# Connectors.net
KiCad netlist of a schematic drawn in Altium Designer
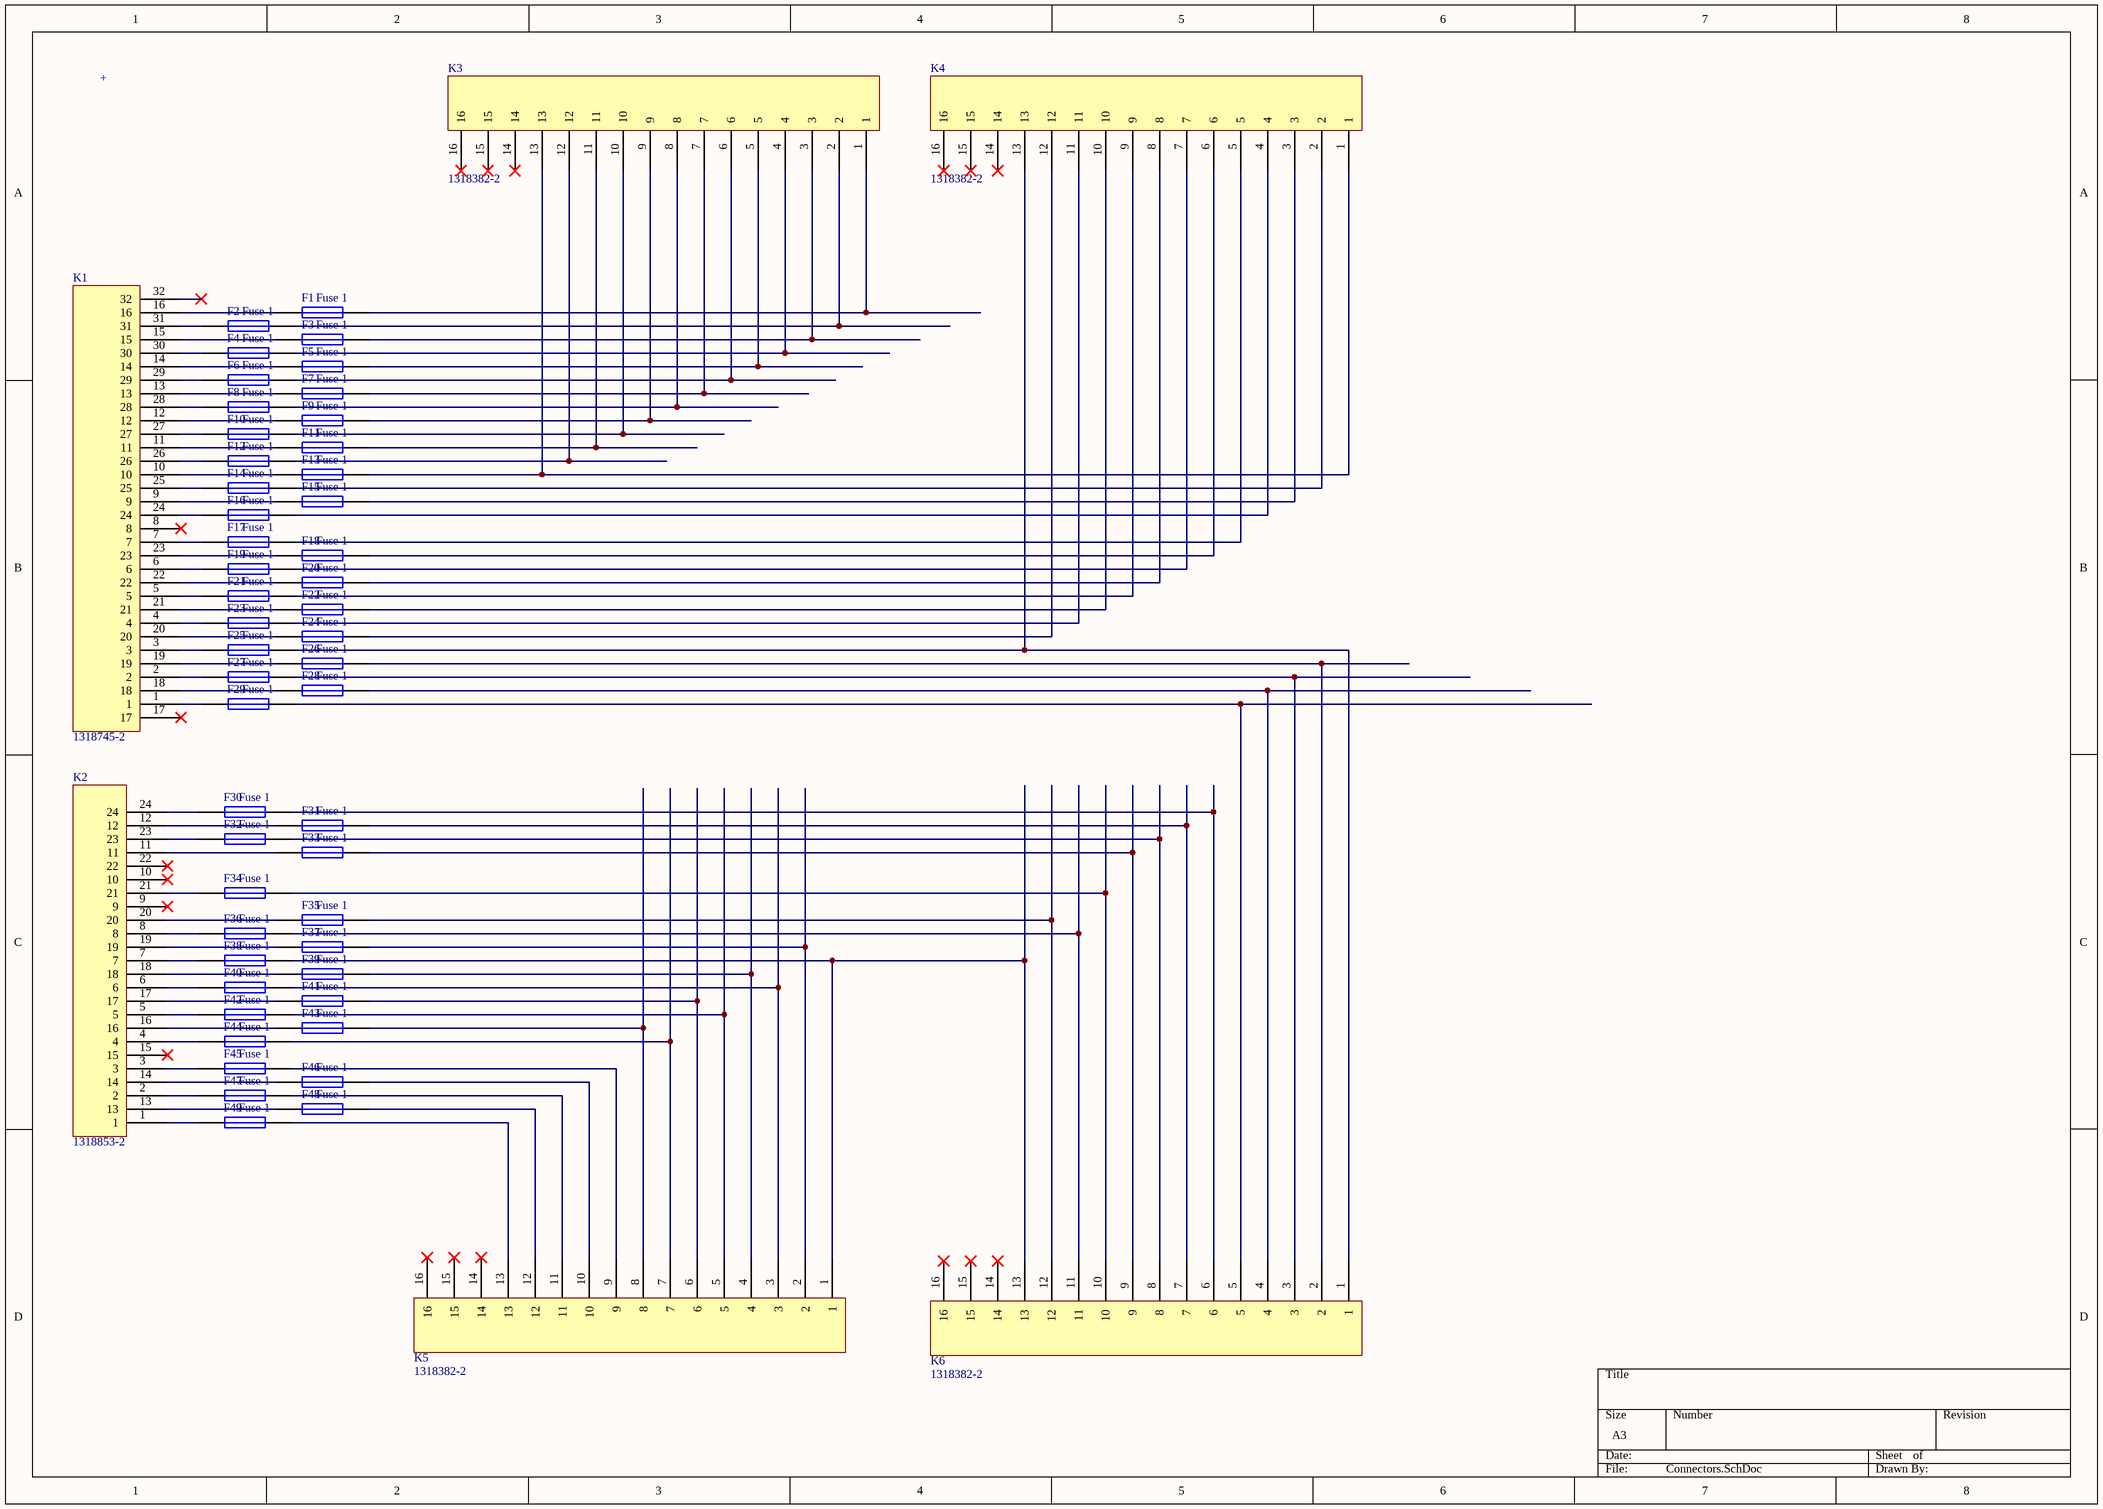
[diagram p0: Connectors.SchDoc]

(export (version "E")
  (design (tool "Eeschema 10.0.6"))
  (components
    (comp (ref "F1")
      (value "Fuse 1")
      (footprint "C1206")
      (description "Fuse")
      (fields (field (name "PUBLISHER") "Altium Limited"))
      (libsource (lib "Miscellaneous Devices") (part "Fuse 1"))
    )
    (comp (ref "F2")
      (value "Fuse 1")
      (footprint "C1206")
      (description "Fuse")
      (fields (field (name "PUBLISHER") "Altium Limited"))
      (libsource (lib "Miscellaneous Devices") (part "Fuse 1"))
    )
    (comp (ref "F3")
      (value "Fuse 1")
      (footprint "C1206")
      (description "Fuse")
      (fields (field (name "PUBLISHER") "Altium Limited"))
      (libsource (lib "Miscellaneous Devices") (part "Fuse 1"))
    )
    (comp (ref "F4")
      (value "Fuse 1")
      (footprint "C1206")
      (description "Fuse")
      (fields (field (name "PUBLISHER") "Altium Limited"))
      (libsource (lib "Miscellaneous Devices") (part "Fuse 1"))
    )
    (comp (ref "F5")
      (value "Fuse 1")
      (footprint "C1206")
      (description "Fuse")
      (fields (field (name "PUBLISHER") "Altium Limited"))
      (libsource (lib "Miscellaneous Devices") (part "Fuse 1"))
    )
    (comp (ref "F6")
      (value "Fuse 1")
      (footprint "C1206")
      (description "Fuse")
      (fields (field (name "PUBLISHER") "Altium Limited"))
      (libsource (lib "Miscellaneous Devices") (part "Fuse 1"))
    )
    (comp (ref "F7")
      (value "Fuse 1")
      (footprint "C1206")
      (description "Fuse")
      (fields (field (name "PUBLISHER") "Altium Limited"))
      (libsource (lib "Miscellaneous Devices") (part "Fuse 1"))
    )
    (comp (ref "F8")
      (value "Fuse 1")
      (footprint "C1206")
      (description "Fuse")
      (fields (field (name "PUBLISHER") "Altium Limited"))
      (libsource (lib "Miscellaneous Devices") (part "Fuse 1"))
    )
    (comp (ref "F9")
      (value "Fuse 1")
      (footprint "C1206")
      (description "Fuse")
      (fields (field (name "PUBLISHER") "Altium Limited"))
      (libsource (lib "Miscellaneous Devices") (part "Fuse 1"))
    )
    (comp (ref "F10")
      (value "Fuse 1")
      (footprint "C1206")
      (description "Fuse")
      (fields (field (name "PUBLISHER") "Altium Limited"))
      (libsource (lib "Miscellaneous Devices") (part "Fuse 1"))
    )
    (comp (ref "F11")
      (value "Fuse 1")
      (footprint "C1206")
      (description "Fuse")
      (fields (field (name "PUBLISHER") "Altium Limited"))
      (libsource (lib "Miscellaneous Devices") (part "Fuse 1"))
    )
    (comp (ref "F12")
      (value "Fuse 1")
      (footprint "C1206")
      (description "Fuse")
      (fields (field (name "PUBLISHER") "Altium Limited"))
      (libsource (lib "Miscellaneous Devices") (part "Fuse 1"))
    )
    (comp (ref "F13")
      (value "Fuse 1")
      (footprint "C1206")
      (description "Fuse")
      (fields (field (name "PUBLISHER") "Altium Limited"))
      (libsource (lib "Miscellaneous Devices") (part "Fuse 1"))
    )
    (comp (ref "F14")
      (value "Fuse 1")
      (footprint "C1206")
      (description "Fuse")
      (fields (field (name "PUBLISHER") "Altium Limited"))
      (libsource (lib "Miscellaneous Devices") (part "Fuse 1"))
    )
    (comp (ref "F15")
      (value "Fuse 1")
      (footprint "C1206")
      (description "Fuse")
      (fields (field (name "PUBLISHER") "Altium Limited"))
      (libsource (lib "Miscellaneous Devices") (part "Fuse 1"))
    )
    (comp (ref "F16")
      (value "Fuse 1")
      (footprint "C1206")
      (description "Fuse")
      (fields (field (name "PUBLISHER") "Altium Limited"))
      (libsource (lib "Miscellaneous Devices") (part "Fuse 1"))
    )
    (comp (ref "F17")
      (value "Fuse 1")
      (footprint "C1206")
      (description "Fuse")
      (fields (field (name "PUBLISHER") "Altium Limited"))
      (libsource (lib "Miscellaneous Devices") (part "Fuse 1"))
    )
    (comp (ref "F18")
      (value "Fuse 1")
      (footprint "C1206")
      (description "Fuse")
      (fields (field (name "PUBLISHER") "Altium Limited"))
      (libsource (lib "Miscellaneous Devices") (part "Fuse 1"))
    )
    (comp (ref "F19")
      (value "Fuse 1")
      (footprint "C1206")
      (description "Fuse")
      (fields (field (name "PUBLISHER") "Altium Limited"))
      (libsource (lib "Miscellaneous Devices") (part "Fuse 1"))
    )
    (comp (ref "F20")
      (value "Fuse 1")
      (footprint "C1206")
      (description "Fuse")
      (fields (field (name "PUBLISHER") "Altium Limited"))
      (libsource (lib "Miscellaneous Devices") (part "Fuse 1"))
    )
    (comp (ref "F21")
      (value "Fuse 1")
      (footprint "C1206")
      (description "Fuse")
      (fields (field (name "PUBLISHER") "Altium Limited"))
      (libsource (lib "Miscellaneous Devices") (part "Fuse 1"))
    )
    (comp (ref "F22")
      (value "Fuse 1")
      (footprint "C1206")
      (description "Fuse")
      (fields (field (name "PUBLISHER") "Altium Limited"))
      (libsource (lib "Miscellaneous Devices") (part "Fuse 1"))
    )
    (comp (ref "F23")
      (value "Fuse 1")
      (footprint "C1206")
      (description "Fuse")
      (fields (field (name "PUBLISHER") "Altium Limited"))
      (libsource (lib "Miscellaneous Devices") (part "Fuse 1"))
    )
    (comp (ref "F24")
      (value "Fuse 1")
      (footprint "C1206")
      (description "Fuse")
      (fields (field (name "PUBLISHER") "Altium Limited"))
      (libsource (lib "Miscellaneous Devices") (part "Fuse 1"))
    )
    (comp (ref "F25")
      (value "Fuse 1")
      (footprint "C1206")
      (description "Fuse")
      (fields (field (name "PUBLISHER") "Altium Limited"))
      (libsource (lib "Miscellaneous Devices") (part "Fuse 1"))
    )
    (comp (ref "F26")
      (value "Fuse 1")
      (footprint "C1206")
      (description "Fuse")
      (fields (field (name "PUBLISHER") "Altium Limited"))
      (libsource (lib "Miscellaneous Devices") (part "Fuse 1"))
    )
    (comp (ref "F27")
      (value "Fuse 1")
      (footprint "C1206")
      (description "Fuse")
      (fields (field (name "PUBLISHER") "Altium Limited"))
      (libsource (lib "Miscellaneous Devices") (part "Fuse 1"))
    )
    (comp (ref "F28")
      (value "Fuse 1")
      (footprint "C1206")
      (description "Fuse")
      (fields (field (name "PUBLISHER") "Altium Limited"))
      (libsource (lib "Miscellaneous Devices") (part "Fuse 1"))
    )
    (comp (ref "F29")
      (value "Fuse 1")
      (footprint "C1206")
      (description "Fuse")
      (fields (field (name "PUBLISHER") "Altium Limited"))
      (libsource (lib "Miscellaneous Devices") (part "Fuse 1"))
    )
    (comp (ref "F30")
      (value "Fuse 1")
      (footprint "C1206")
      (description "Fuse")
      (fields (field (name "PUBLISHER") "Altium Limited"))
      (libsource (lib "Miscellaneous Devices") (part "Fuse 1"))
    )
    (comp (ref "F31")
      (value "Fuse 1")
      (footprint "C1206")
      (description "Fuse")
      (fields (field (name "PUBLISHER") "Altium Limited"))
      (libsource (lib "Miscellaneous Devices") (part "Fuse 1"))
    )
    (comp (ref "F32")
      (value "Fuse 1")
      (footprint "C1206")
      (description "Fuse")
      (fields (field (name "PUBLISHER") "Altium Limited"))
      (libsource (lib "Miscellaneous Devices") (part "Fuse 1"))
    )
    (comp (ref "F33")
      (value "Fuse 1")
      (footprint "C1206")
      (description "Fuse")
      (fields (field (name "PUBLISHER") "Altium Limited"))
      (libsource (lib "Miscellaneous Devices") (part "Fuse 1"))
    )
    (comp (ref "F34")
      (value "Fuse 1")
      (footprint "C1206")
      (description "Fuse")
      (fields (field (name "PUBLISHER") "Altium Limited"))
      (libsource (lib "Miscellaneous Devices") (part "Fuse 1"))
    )
    (comp (ref "F35")
      (value "Fuse 1")
      (footprint "C1206")
      (description "Fuse")
      (fields (field (name "PUBLISHER") "Altium Limited"))
      (libsource (lib "Miscellaneous Devices") (part "Fuse 1"))
    )
    (comp (ref "F36")
      (value "Fuse 1")
      (footprint "C1206")
      (description "Fuse")
      (fields (field (name "PUBLISHER") "Altium Limited"))
      (libsource (lib "Miscellaneous Devices") (part "Fuse 1"))
    )
    (comp (ref "F37")
      (value "Fuse 1")
      (footprint "C1206")
      (description "Fuse")
      (fields (field (name "PUBLISHER") "Altium Limited"))
      (libsource (lib "Miscellaneous Devices") (part "Fuse 1"))
    )
    (comp (ref "F38")
      (value "Fuse 1")
      (footprint "C1206")
      (description "Fuse")
      (fields (field (name "PUBLISHER") "Altium Limited"))
      (libsource (lib "Miscellaneous Devices") (part "Fuse 1"))
    )
    (comp (ref "F39")
      (value "Fuse 1")
      (footprint "C1206")
      (description "Fuse")
      (fields (field (name "PUBLISHER") "Altium Limited"))
      (libsource (lib "Miscellaneous Devices") (part "Fuse 1"))
    )
    (comp (ref "F40")
      (value "Fuse 1")
      (footprint "C1206")
      (description "Fuse")
      (fields (field (name "PUBLISHER") "Altium Limited"))
      (libsource (lib "Miscellaneous Devices") (part "Fuse 1"))
    )
    (comp (ref "F41")
      (value "Fuse 1")
      (footprint "C1206")
      (description "Fuse")
      (fields (field (name "PUBLISHER") "Altium Limited"))
      (libsource (lib "Miscellaneous Devices") (part "Fuse 1"))
    )
    (comp (ref "F42")
      (value "Fuse 1")
      (footprint "C1206")
      (description "Fuse")
      (fields (field (name "PUBLISHER") "Altium Limited"))
      (libsource (lib "Miscellaneous Devices") (part "Fuse 1"))
    )
    (comp (ref "F43")
      (value "Fuse 1")
      (footprint "C1206")
      (description "Fuse")
      (fields (field (name "PUBLISHER") "Altium Limited"))
      (libsource (lib "Miscellaneous Devices") (part "Fuse 1"))
    )
    (comp (ref "F44")
      (value "Fuse 1")
      (footprint "C1206")
      (description "Fuse")
      (fields (field (name "PUBLISHER") "Altium Limited"))
      (libsource (lib "Miscellaneous Devices") (part "Fuse 1"))
    )
    (comp (ref "F45")
      (value "Fuse 1")
      (footprint "C1206")
      (description "Fuse")
      (fields (field (name "PUBLISHER") "Altium Limited"))
      (libsource (lib "Miscellaneous Devices") (part "Fuse 1"))
    )
    (comp (ref "F46")
      (value "Fuse 1")
      (footprint "C1206")
      (description "Fuse")
      (fields (field (name "PUBLISHER") "Altium Limited"))
      (libsource (lib "Miscellaneous Devices") (part "Fuse 1"))
    )
    (comp (ref "F47")
      (value "Fuse 1")
      (footprint "C1206")
      (description "Fuse")
      (fields (field (name "PUBLISHER") "Altium Limited"))
      (libsource (lib "Miscellaneous Devices") (part "Fuse 1"))
    )
    (comp (ref "F48")
      (value "Fuse 1")
      (footprint "C1206")
      (description "Fuse")
      (fields (field (name "PUBLISHER") "Altium Limited"))
      (libsource (lib "Miscellaneous Devices") (part "Fuse 1"))
    )
    (comp (ref "F49")
      (value "Fuse 1")
      (footprint "C1206")
      (description "Fuse")
      (fields (field (name "PUBLISHER") "Altium Limited"))
      (libsource (lib "Miscellaneous Devices") (part "Fuse 1"))
    )
    (comp (ref "K1")
      (value "1318745-2")
      (footprint "1318745-2")
      (libsource (lib "TE connectivity") (part "1318745-2"))
    )
    (comp (ref "K2")
      (value "1318853-2")
      (footprint "1318853-2")
      (libsource (lib "TE connectivity") (part "1318853-2"))
    )
    (comp (ref "K3") (value "1318382-2") (footprint "1318382-2") (libsource (lib "") (part "1318382-2_1")))
    (comp (ref "K4") (value "1318382-2") (footprint "1318382-2") (libsource (lib "") (part "1318382-2_1")))
    (comp (ref "K5")
      (value "1318382-2")
      (footprint "1318382-2")
      (libsource (lib "TE connectivity") (part "1318382-2"))
    )
    (comp (ref "K6")
      (value "1318382-2")
      (footprint "1318382-2")
      (libsource (lib "TE connectivity") (part "1318382-2"))
    )
  )
  (nets
    (net (code "1") (name "Net-(F1-Pad1)") (class "Default")
      (node (ref "F1") (pin "1") (pinfunction "1_1") (pintype "passive"))
      (node (ref "K1") (pin "16") (pinfunction "16_16") (pintype "passive"))
    )
    (net (code "2") (name "Net-(F1-Pad2)") (class "Default")
      (node (ref "F1") (pin "2") (pinfunction "2_2") (pintype "passive"))
      (node (ref "K3") (pin "1") (pinfunction "1_1") (pintype "passive"))
    )
    (net (code "3") (name "Net-(F2-Pad1)") (class "Default")
      (node (ref "F2") (pin "1") (pinfunction "1_1") (pintype "passive"))
      (node (ref "K1") (pin "31") (pinfunction "31_31") (pintype "passive"))
    )
    (net (code "4") (name "Net-(F2-Pad2)") (class "Default")
      (node (ref "F2") (pin "2") (pinfunction "2_2") (pintype "passive"))
      (node (ref "K3") (pin "2") (pinfunction "2_2") (pintype "passive"))
    )
    (net (code "5") (name "Net-(F3-Pad1)") (class "Default")
      (node (ref "F3") (pin "1") (pinfunction "1_1") (pintype "passive"))
      (node (ref "K1") (pin "15") (pinfunction "15_15") (pintype "passive"))
    )
    (net (code "6") (name "Net-(F3-Pad2)") (class "Default")
      (node (ref "F3") (pin "2") (pinfunction "2_2") (pintype "passive"))
      (node (ref "K3") (pin "3") (pinfunction "3_3") (pintype "passive"))
    )
    (net (code "7") (name "Net-(F4-Pad1)") (class "Default")
      (node (ref "F4") (pin "1") (pinfunction "1_1") (pintype "passive"))
      (node (ref "K1") (pin "30") (pinfunction "30_30") (pintype "passive"))
    )
    (net (code "8") (name "Net-(F4-Pad2)") (class "Default")
      (node (ref "F4") (pin "2") (pinfunction "2_2") (pintype "passive"))
      (node (ref "K3") (pin "4") (pinfunction "4_4") (pintype "passive"))
    )
    (net (code "9") (name "Net-(F5-Pad1)") (class "Default")
      (node (ref "F5") (pin "1") (pinfunction "1_1") (pintype "passive"))
      (node (ref "K1") (pin "14") (pinfunction "14_14") (pintype "passive"))
    )
    (net (code "10") (name "Net-(F5-Pad2)") (class "Default")
      (node (ref "F5") (pin "2") (pinfunction "2_2") (pintype "passive"))
      (node (ref "K3") (pin "5") (pinfunction "5_5") (pintype "passive"))
    )
    (net (code "11") (name "Net-(F6-Pad1)") (class "Default")
      (node (ref "F6") (pin "1") (pinfunction "1_1") (pintype "passive"))
      (node (ref "K1") (pin "29") (pinfunction "29_29") (pintype "passive"))
    )
    (net (code "12") (name "Net-(F6-Pad2)") (class "Default")
      (node (ref "F6") (pin "2") (pinfunction "2_2") (pintype "passive"))
      (node (ref "K3") (pin "6") (pinfunction "6_6") (pintype "passive"))
    )
    (net (code "13") (name "Net-(F7-Pad1)") (class "Default")
      (node (ref "F7") (pin "1") (pinfunction "1_1") (pintype "passive"))
      (node (ref "K1") (pin "13") (pinfunction "13_13") (pintype "passive"))
    )
    (net (code "14") (name "Net-(F7-Pad2)") (class "Default")
      (node (ref "F7") (pin "2") (pinfunction "2_2") (pintype "passive"))
      (node (ref "K3") (pin "7") (pinfunction "7_7") (pintype "passive"))
    )
    (net (code "15") (name "Net-(F8-Pad1)") (class "Default")
      (node (ref "F8") (pin "1") (pinfunction "1_1") (pintype "passive"))
      (node (ref "K1") (pin "28") (pinfunction "28_28") (pintype "passive"))
    )
    (net (code "16") (name "Net-(F8-Pad2)") (class "Default")
      (node (ref "F8") (pin "2") (pinfunction "2_2") (pintype "passive"))
      (node (ref "K3") (pin "8") (pinfunction "8_8") (pintype "passive"))
    )
    (net (code "17") (name "Net-(F9-Pad1)") (class "Default")
      (node (ref "F9") (pin "1") (pinfunction "1_1") (pintype "passive"))
      (node (ref "K1") (pin "12") (pinfunction "12_12") (pintype "passive"))
    )
    (net (code "18") (name "Net-(F9-Pad2)") (class "Default")
      (node (ref "F9") (pin "2") (pinfunction "2_2") (pintype "passive"))
      (node (ref "K3") (pin "9") (pinfunction "9_9") (pintype "passive"))
    )
    (net (code "19") (name "Net-(F10-Pad1)") (class "Default")
      (node (ref "F10") (pin "1") (pinfunction "1_1") (pintype "passive"))
      (node (ref "K1") (pin "27") (pinfunction "27_27") (pintype "passive"))
    )
    (net (code "20") (name "Net-(F10-Pad2)") (class "Default")
      (node (ref "F10") (pin "2") (pinfunction "2_2") (pintype "passive"))
      (node (ref "K3") (pin "10") (pinfunction "10_10") (pintype "passive"))
    )
    (net (code "21") (name "Net-(F11-Pad1)") (class "Default")
      (node (ref "F11") (pin "1") (pinfunction "1_1") (pintype "passive"))
      (node (ref "K1") (pin "11") (pinfunction "11_11") (pintype "passive"))
    )
    (net (code "22") (name "Net-(F11-Pad2)") (class "Default")
      (node (ref "F11") (pin "2") (pinfunction "2_2") (pintype "passive"))
      (node (ref "K3") (pin "11") (pinfunction "11_11") (pintype "passive"))
    )
    (net (code "23") (name "Net-(F12-Pad1)") (class "Default")
      (node (ref "F12") (pin "1") (pinfunction "1_1") (pintype "passive"))
      (node (ref "K1") (pin "26") (pinfunction "26_26") (pintype "passive"))
    )
    (net (code "24") (name "Net-(F12-Pad2)") (class "Default")
      (node (ref "F12") (pin "2") (pinfunction "2_2") (pintype "passive"))
      (node (ref "K3") (pin "12") (pinfunction "12_12") (pintype "passive"))
    )
    (net (code "25") (name "Net-(F13-Pad1)") (class "Default")
      (node (ref "F13") (pin "1") (pinfunction "1_1") (pintype "passive"))
      (node (ref "K1") (pin "10") (pinfunction "10_10") (pintype "passive"))
    )
    (net (code "26") (name "Net-(F13-Pad2)") (class "Default")
      (node (ref "F13") (pin "2") (pinfunction "2_2") (pintype "passive"))
      (node (ref "K3") (pin "13") (pinfunction "13_13") (pintype "passive"))
      (node (ref "K4") (pin "1") (pinfunction "1_1") (pintype "passive"))
    )
    (net (code "27") (name "Net-(F14-Pad1)") (class "Default")
      (node (ref "F14") (pin "1") (pinfunction "1_1") (pintype "passive"))
      (node (ref "K1") (pin "25") (pinfunction "25_25") (pintype "passive"))
    )
    (net (code "28") (name "Net-(F14-Pad2)") (class "Default")
      (node (ref "F14") (pin "2") (pinfunction "2_2") (pintype "passive"))
      (node (ref "K4") (pin "2") (pinfunction "2_2") (pintype "passive"))
    )
    (net (code "29") (name "Net-(F15-Pad1)") (class "Default")
      (node (ref "F15") (pin "1") (pinfunction "1_1") (pintype "passive"))
      (node (ref "K1") (pin "9") (pinfunction "9_9") (pintype "passive"))
    )
    (net (code "30") (name "Net-(F15-Pad2)") (class "Default")
      (node (ref "F15") (pin "2") (pinfunction "2_2") (pintype "passive"))
      (node (ref "K4") (pin "3") (pinfunction "3_3") (pintype "passive"))
    )
    (net (code "31") (name "Net-(F16-Pad1)") (class "Default")
      (node (ref "F16") (pin "1") (pinfunction "1_1") (pintype "passive"))
      (node (ref "K1") (pin "24") (pinfunction "24_24") (pintype "passive"))
    )
    (net (code "32") (name "Net-(F16-Pad2)") (class "Default")
      (node (ref "F16") (pin "2") (pinfunction "2_2") (pintype "passive"))
      (node (ref "K4") (pin "4") (pinfunction "4_4") (pintype "passive"))
    )
    (net (code "33") (name "Net-(F17-Pad1)") (class "Default")
      (node (ref "F17") (pin "1") (pinfunction "1_1") (pintype "passive"))
      (node (ref "K1") (pin "7") (pinfunction "7_7") (pintype "passive"))
    )
    (net (code "34") (name "Net-(F17-Pad2)") (class "Default")
      (node (ref "F17") (pin "2") (pinfunction "2_2") (pintype "passive"))
      (node (ref "K4") (pin "5") (pinfunction "5_5") (pintype "passive"))
    )
    (net (code "35") (name "Net-(F18-Pad1)") (class "Default")
      (node (ref "F18") (pin "1") (pinfunction "1_1") (pintype "passive"))
      (node (ref "K1") (pin "23") (pinfunction "23_23") (pintype "passive"))
    )
    (net (code "36") (name "Net-(F18-Pad2)") (class "Default")
      (node (ref "F18") (pin "2") (pinfunction "2_2") (pintype "passive"))
      (node (ref "K4") (pin "6") (pinfunction "6_6") (pintype "passive"))
    )
    (net (code "37") (name "Net-(F19-Pad1)") (class "Default")
      (node (ref "F19") (pin "1") (pinfunction "1_1") (pintype "passive"))
      (node (ref "K1") (pin "6") (pinfunction "6_6") (pintype "passive"))
    )
    (net (code "38") (name "Net-(F19-Pad2)") (class "Default")
      (node (ref "F19") (pin "2") (pinfunction "2_2") (pintype "passive"))
      (node (ref "K4") (pin "7") (pinfunction "7_7") (pintype "passive"))
    )
    (net (code "39") (name "Net-(F20-Pad1)") (class "Default")
      (node (ref "F20") (pin "1") (pinfunction "1_1") (pintype "passive"))
      (node (ref "K1") (pin "22") (pinfunction "22_22") (pintype "passive"))
    )
    (net (code "40") (name "Net-(F20-Pad2)") (class "Default")
      (node (ref "F20") (pin "2") (pinfunction "2_2") (pintype "passive"))
      (node (ref "K4") (pin "8") (pinfunction "8_8") (pintype "passive"))
    )
    (net (code "41") (name "Net-(F21-Pad1)") (class "Default")
      (node (ref "F21") (pin "1") (pinfunction "1_1") (pintype "passive"))
      (node (ref "K1") (pin "5") (pinfunction "5_5") (pintype "passive"))
    )
    (net (code "42") (name "Net-(F21-Pad2)") (class "Default")
      (node (ref "F21") (pin "2") (pinfunction "2_2") (pintype "passive"))
      (node (ref "K4") (pin "9") (pinfunction "9_9") (pintype "passive"))
    )
    (net (code "43") (name "Net-(F22-Pad1)") (class "Default")
      (node (ref "F22") (pin "1") (pinfunction "1_1") (pintype "passive"))
      (node (ref "K1") (pin "21") (pinfunction "21_21") (pintype "passive"))
    )
    (net (code "44") (name "Net-(F22-Pad2)") (class "Default")
      (node (ref "F22") (pin "2") (pinfunction "2_2") (pintype "passive"))
      (node (ref "K4") (pin "10") (pinfunction "10_10") (pintype "passive"))
    )
    (net (code "45") (name "Net-(F23-Pad1)") (class "Default")
      (node (ref "F23") (pin "1") (pinfunction "1_1") (pintype "passive"))
      (node (ref "K1") (pin "4") (pinfunction "4_4") (pintype "passive"))
    )
    (net (code "46") (name "Net-(F23-Pad2)") (class "Default")
      (node (ref "F23") (pin "2") (pinfunction "2_2") (pintype "passive"))
      (node (ref "K4") (pin "11") (pinfunction "11_11") (pintype "passive"))
    )
    (net (code "47") (name "Net-(F24-Pad1)") (class "Default")
      (node (ref "F24") (pin "1") (pinfunction "1_1") (pintype "passive"))
      (node (ref "K1") (pin "20") (pinfunction "20_20") (pintype "passive"))
    )
    (net (code "48") (name "Net-(F24-Pad2)") (class "Default")
      (node (ref "F24") (pin "2") (pinfunction "2_2") (pintype "passive"))
      (node (ref "K4") (pin "12") (pinfunction "12_12") (pintype "passive"))
    )
    (net (code "49") (name "Net-(F25-Pad1)") (class "Default")
      (node (ref "F25") (pin "1") (pinfunction "1_1") (pintype "passive"))
      (node (ref "K1") (pin "3") (pinfunction "3_3") (pintype "passive"))
    )
    (net (code "50") (name "Net-(F25-Pad2)") (class "Default")
      (node (ref "F25") (pin "2") (pinfunction "2_2") (pintype "passive"))
      (node (ref "K4") (pin "13") (pinfunction "13_13") (pintype "passive"))
      (node (ref "K6") (pin "1") (pinfunction "1_1") (pintype "passive"))
    )
    (net (code "51") (name "Net-(F26-Pad1)") (class "Default")
      (node (ref "F26") (pin "1") (pinfunction "1_1") (pintype "passive"))
      (node (ref "K1") (pin "19") (pinfunction "19_19") (pintype "passive"))
    )
    (net (code "52") (name "Net-(F26-Pad2)") (class "Default")
      (node (ref "F26") (pin "2") (pinfunction "2_2") (pintype "passive"))
      (node (ref "K6") (pin "2") (pinfunction "2_2") (pintype "passive"))
    )
    (net (code "53") (name "Net-(F27-Pad1)") (class "Default")
      (node (ref "F27") (pin "1") (pinfunction "1_1") (pintype "passive"))
      (node (ref "K1") (pin "2") (pinfunction "2_2") (pintype "passive"))
    )
    (net (code "54") (name "Net-(F27-Pad2)") (class "Default")
      (node (ref "F27") (pin "2") (pinfunction "2_2") (pintype "passive"))
      (node (ref "K6") (pin "3") (pinfunction "3_3") (pintype "passive"))
    )
    (net (code "55") (name "Net-(F28-Pad1)") (class "Default")
      (node (ref "F28") (pin "1") (pinfunction "1_1") (pintype "passive"))
      (node (ref "K1") (pin "18") (pinfunction "18_18") (pintype "passive"))
    )
    (net (code "56") (name "Net-(F28-Pad2)") (class "Default")
      (node (ref "F28") (pin "2") (pinfunction "2_2") (pintype "passive"))
      (node (ref "K6") (pin "4") (pinfunction "4_4") (pintype "passive"))
    )
    (net (code "57") (name "Net-(F29-Pad1)") (class "Default")
      (node (ref "F29") (pin "1") (pinfunction "1_1") (pintype "passive"))
      (node (ref "K1") (pin "1") (pinfunction "1_1") (pintype "passive"))
    )
    (net (code "58") (name "Net-(F29-Pad2)") (class "Default")
      (node (ref "F29") (pin "2") (pinfunction "2_2") (pintype "passive"))
      (node (ref "K6") (pin "5") (pinfunction "5_5") (pintype "passive"))
    )
    (net (code "59") (name "Net-(F30-Pad1)") (class "Default")
      (node (ref "F30") (pin "1") (pinfunction "1_1") (pintype "passive"))
      (node (ref "K2") (pin "24") (pinfunction "24_24") (pintype "passive"))
    )
    (net (code "60") (name "Net-(F30-Pad2)") (class "Default")
      (node (ref "F30") (pin "2") (pinfunction "2_2") (pintype "passive"))
      (node (ref "K6") (pin "6") (pinfunction "6_6") (pintype "passive"))
    )
    (net (code "61") (name "Net-(F31-Pad1)") (class "Default")
      (node (ref "F31") (pin "1") (pinfunction "1_1") (pintype "passive"))
      (node (ref "K2") (pin "12") (pinfunction "12_12") (pintype "passive"))
    )
    (net (code "62") (name "Net-(F31-Pad2)") (class "Default")
      (node (ref "F31") (pin "2") (pinfunction "2_2") (pintype "passive"))
      (node (ref "K6") (pin "7") (pinfunction "7_7") (pintype "passive"))
    )
    (net (code "63") (name "Net-(F32-Pad1)") (class "Default")
      (node (ref "F32") (pin "1") (pinfunction "1_1") (pintype "passive"))
      (node (ref "K2") (pin "23") (pinfunction "23_23") (pintype "passive"))
    )
    (net (code "64") (name "Net-(F32-Pad2)") (class "Default")
      (node (ref "F32") (pin "2") (pinfunction "2_2") (pintype "passive"))
      (node (ref "K6") (pin "8") (pinfunction "8_8") (pintype "passive"))
    )
    (net (code "65") (name "Net-(F33-Pad1)") (class "Default")
      (node (ref "F33") (pin "1") (pinfunction "1_1") (pintype "passive"))
      (node (ref "K2") (pin "11") (pinfunction "11_11") (pintype "passive"))
    )
    (net (code "66") (name "Net-(F33-Pad2)") (class "Default")
      (node (ref "F33") (pin "2") (pinfunction "2_2") (pintype "passive"))
      (node (ref "K6") (pin "9") (pinfunction "9_9") (pintype "passive"))
    )
    (net (code "67") (name "Net-(F34-Pad1)") (class "Default")
      (node (ref "F34") (pin "1") (pinfunction "1_1") (pintype "passive"))
      (node (ref "K2") (pin "21") (pinfunction "21_21") (pintype "passive"))
    )
    (net (code "68") (name "Net-(F34-Pad2)") (class "Default")
      (node (ref "F34") (pin "2") (pinfunction "2_2") (pintype "passive"))
      (node (ref "K6") (pin "10") (pinfunction "10_10") (pintype "passive"))
    )
    (net (code "69") (name "Net-(F35-Pad1)") (class "Default")
      (node (ref "F35") (pin "1") (pinfunction "1_1") (pintype "passive"))
      (node (ref "K2") (pin "20") (pinfunction "20_20") (pintype "passive"))
    )
    (net (code "70") (name "Net-(F35-Pad2)") (class "Default")
      (node (ref "F35") (pin "2") (pinfunction "2_2") (pintype "passive"))
      (node (ref "K6") (pin "12") (pinfunction "12_12") (pintype "passive"))
    )
    (net (code "71") (name "Net-(F36-Pad1)") (class "Default")
      (node (ref "F36") (pin "1") (pinfunction "1_1") (pintype "passive"))
      (node (ref "K2") (pin "8") (pinfunction "8_8") (pintype "passive"))
    )
    (net (code "72") (name "Net-(F36-Pad2)") (class "Default")
      (node (ref "F36") (pin "2") (pinfunction "2_2") (pintype "passive"))
      (node (ref "K6") (pin "11") (pinfunction "11_11") (pintype "passive"))
    )
    (net (code "73") (name "Net-(F37-Pad1)") (class "Default")
      (node (ref "F37") (pin "1") (pinfunction "1_1") (pintype "passive"))
      (node (ref "K2") (pin "19") (pinfunction "19_19") (pintype "passive"))
    )
    (net (code "74") (name "Net-(F37-Pad2)") (class "Default")
      (node (ref "F37") (pin "2") (pinfunction "2_2") (pintype "passive"))
      (node (ref "K5") (pin "2") (pinfunction "2_2") (pintype "passive"))
    )
    (net (code "75") (name "Net-(F38-Pad1)") (class "Default")
      (node (ref "F38") (pin "1") (pinfunction "1_1") (pintype "passive"))
      (node (ref "K2") (pin "7") (pinfunction "7_7") (pintype "passive"))
    )
    (net (code "76") (name "Net-(F38-Pad2)") (class "Default")
      (node (ref "F38") (pin "2") (pinfunction "2_2") (pintype "passive"))
      (node (ref "K5") (pin "1") (pinfunction "1_1") (pintype "passive"))
      (node (ref "K6") (pin "13") (pinfunction "13_13") (pintype "passive"))
    )
    (net (code "77") (name "Net-(F39-Pad1)") (class "Default")
      (node (ref "F39") (pin "1") (pinfunction "1_1") (pintype "passive"))
      (node (ref "K2") (pin "18") (pinfunction "18_18") (pintype "passive"))
    )
    (net (code "78") (name "Net-(F39-Pad2)") (class "Default")
      (node (ref "F39") (pin "2") (pinfunction "2_2") (pintype "passive"))
      (node (ref "K5") (pin "4") (pinfunction "4_4") (pintype "passive"))
    )
    (net (code "79") (name "Net-(F40-Pad1)") (class "Default")
      (node (ref "F40") (pin "1") (pinfunction "1_1") (pintype "passive"))
      (node (ref "K2") (pin "6") (pinfunction "6_6") (pintype "passive"))
    )
    (net (code "80") (name "Net-(F40-Pad2)") (class "Default")
      (node (ref "F40") (pin "2") (pinfunction "2_2") (pintype "passive"))
      (node (ref "K5") (pin "3") (pinfunction "3_3") (pintype "passive"))
    )
    (net (code "81") (name "Net-(F41-Pad1)") (class "Default")
      (node (ref "F41") (pin "1") (pinfunction "1_1") (pintype "passive"))
      (node (ref "K2") (pin "17") (pinfunction "17_17") (pintype "passive"))
    )
    (net (code "82") (name "Net-(F41-Pad2)") (class "Default")
      (node (ref "F41") (pin "2") (pinfunction "2_2") (pintype "passive"))
      (node (ref "K5") (pin "6") (pinfunction "6_6") (pintype "passive"))
    )
    (net (code "83") (name "Net-(F42-Pad1)") (class "Default")
      (node (ref "F42") (pin "1") (pinfunction "1_1") (pintype "passive"))
      (node (ref "K2") (pin "5") (pinfunction "5_5") (pintype "passive"))
    )
    (net (code "84") (name "Net-(F42-Pad2)") (class "Default")
      (node (ref "F42") (pin "2") (pinfunction "2_2") (pintype "passive"))
      (node (ref "K5") (pin "5") (pinfunction "5_5") (pintype "passive"))
    )
    (net (code "85") (name "Net-(F43-Pad1)") (class "Default")
      (node (ref "F43") (pin "1") (pinfunction "1_1") (pintype "passive"))
      (node (ref "K2") (pin "16") (pinfunction "16_16") (pintype "passive"))
    )
    (net (code "86") (name "Net-(F43-Pad2)") (class "Default")
      (node (ref "F43") (pin "2") (pinfunction "2_2") (pintype "passive"))
      (node (ref "K5") (pin "8") (pinfunction "8_8") (pintype "passive"))
    )
    (net (code "87") (name "Net-(F44-Pad1)") (class "Default")
      (node (ref "F44") (pin "1") (pinfunction "1_1") (pintype "passive"))
      (node (ref "K2") (pin "4") (pinfunction "4_4") (pintype "passive"))
    )
    (net (code "88") (name "Net-(F44-Pad2)") (class "Default")
      (node (ref "F44") (pin "2") (pinfunction "2_2") (pintype "passive"))
      (node (ref "K5") (pin "7") (pinfunction "7_7") (pintype "passive"))
    )
    (net (code "89") (name "Net-(F45-Pad1)") (class "Default")
      (node (ref "F45") (pin "1") (pinfunction "1_1") (pintype "passive"))
      (node (ref "K2") (pin "3") (pinfunction "3_3") (pintype "passive"))
    )
    (net (code "90") (name "Net-(F45-Pad2)") (class "Default")
      (node (ref "F45") (pin "2") (pinfunction "2_2") (pintype "passive"))
      (node (ref "K5") (pin "9") (pinfunction "9_9") (pintype "passive"))
    )
    (net (code "91") (name "Net-(F46-Pad1)") (class "Default")
      (node (ref "F46") (pin "1") (pinfunction "1_1") (pintype "passive"))
      (node (ref "K2") (pin "14") (pinfunction "14_14") (pintype "passive"))
    )
    (net (code "92") (name "Net-(F46-Pad2)") (class "Default")
      (node (ref "F46") (pin "2") (pinfunction "2_2") (pintype "passive"))
      (node (ref "K5") (pin "10") (pinfunction "10_10") (pintype "passive"))
    )
    (net (code "93") (name "Net-(F47-Pad1)") (class "Default")
      (node (ref "F47") (pin "1") (pinfunction "1_1") (pintype "passive"))
      (node (ref "K2") (pin "2") (pinfunction "2_2") (pintype "passive"))
    )
    (net (code "94") (name "Net-(F47-Pad2)") (class "Default")
      (node (ref "F47") (pin "2") (pinfunction "2_2") (pintype "passive"))
      (node (ref "K5") (pin "11") (pinfunction "11_11") (pintype "passive"))
    )
    (net (code "95") (name "Net-(F48-Pad1)") (class "Default")
      (node (ref "F48") (pin "1") (pinfunction "1_1") (pintype "passive"))
      (node (ref "K2") (pin "13") (pinfunction "13_13") (pintype "passive"))
    )
    (net (code "96") (name "Net-(F48-Pad2)") (class "Default")
      (node (ref "F48") (pin "2") (pinfunction "2_2") (pintype "passive"))
      (node (ref "K5") (pin "12") (pinfunction "12_12") (pintype "passive"))
    )
    (net (code "97") (name "Net-(F49-Pad1)") (class "Default")
      (node (ref "F49") (pin "1") (pinfunction "1_1") (pintype "passive"))
      (node (ref "K2") (pin "1") (pinfunction "1_1") (pintype "passive"))
    )
    (net (code "98") (name "Net-(F49-Pad2)") (class "Default")
      (node (ref "F49") (pin "2") (pinfunction "2_2") (pintype "passive"))
      (node (ref "K5") (pin "13") (pinfunction "13_13") (pintype "passive"))
    )
    (net (code "99") (name "unconnected-(K1-Pad8)") (class "Default")
      (node (ref "K1") (pin "8") (pinfunction "8_8") (pintype "passive+no_connect"))
    )
    (net (code "100") (name "unconnected-(K1-Pad17)") (class "Default")
      (node (ref "K1") (pin "17") (pinfunction "17_17") (pintype "passive+no_connect"))
    )
    (net (code "101") (name "unconnected-(K1-Pad32)") (class "Default")
      (node (ref "K1") (pin "32") (pinfunction "32_32") (pintype "passive+no_connect"))
    )
    (net (code "102") (name "unconnected-(K2-Pad9)") (class "Default")
      (node (ref "K2") (pin "9") (pinfunction "9_9") (pintype "passive+no_connect"))
    )
    (net (code "103") (name "unconnected-(K2-Pad10)") (class "Default")
      (node (ref "K2") (pin "10") (pinfunction "10_10") (pintype "passive+no_connect"))
    )
    (net (code "104") (name "unconnected-(K2-Pad15)") (class "Default")
      (node (ref "K2") (pin "15") (pinfunction "15_15") (pintype "passive+no_connect"))
    )
    (net (code "105") (name "unconnected-(K2-Pad22)") (class "Default")
      (node (ref "K2") (pin "22") (pinfunction "22_22") (pintype "passive+no_connect"))
    )
    (net (code "106") (name "unconnected-(K3-Pad14)") (class "Default")
      (node (ref "K3") (pin "14") (pinfunction "14_14") (pintype "passive+no_connect"))
    )
    (net (code "107") (name "unconnected-(K3-Pad15)") (class "Default")
      (node (ref "K3") (pin "15") (pinfunction "15_15") (pintype "passive+no_connect"))
    )
    (net (code "108") (name "unconnected-(K3-Pad16)") (class "Default")
      (node (ref "K3") (pin "16") (pinfunction "16_16") (pintype "passive+no_connect"))
    )
    (net (code "109") (name "unconnected-(K4-Pad14)") (class "Default")
      (node (ref "K4") (pin "14") (pinfunction "14_14") (pintype "passive+no_connect"))
    )
    (net (code "110") (name "unconnected-(K4-Pad15)") (class "Default")
      (node (ref "K4") (pin "15") (pinfunction "15_15") (pintype "passive+no_connect"))
    )
    (net (code "111") (name "unconnected-(K4-Pad16)") (class "Default")
      (node (ref "K4") (pin "16") (pinfunction "16_16") (pintype "passive+no_connect"))
    )
    (net (code "112") (name "unconnected-(K5-Pad14)") (class "Default")
      (node (ref "K5") (pin "14") (pinfunction "14_14") (pintype "passive+no_connect"))
    )
    (net (code "113") (name "unconnected-(K5-Pad15)") (class "Default")
      (node (ref "K5") (pin "15") (pinfunction "15_15") (pintype "passive+no_connect"))
    )
    (net (code "114") (name "unconnected-(K5-Pad16)") (class "Default")
      (node (ref "K5") (pin "16") (pinfunction "16_16") (pintype "passive+no_connect"))
    )
    (net (code "115") (name "unconnected-(K6-Pad14)") (class "Default")
      (node (ref "K6") (pin "14") (pinfunction "14_14") (pintype "passive+no_connect"))
    )
    (net (code "116") (name "unconnected-(K6-Pad15)") (class "Default")
      (node (ref "K6") (pin "15") (pinfunction "15_15") (pintype "passive+no_connect"))
    )
    (net (code "117") (name "unconnected-(K6-Pad16)") (class "Default")
      (node (ref "K6") (pin "16") (pinfunction "16_16") (pintype "passive+no_connect"))
    )
  )
)
